# board.net
KiCad netlist of a schematic drawn in EAGLE
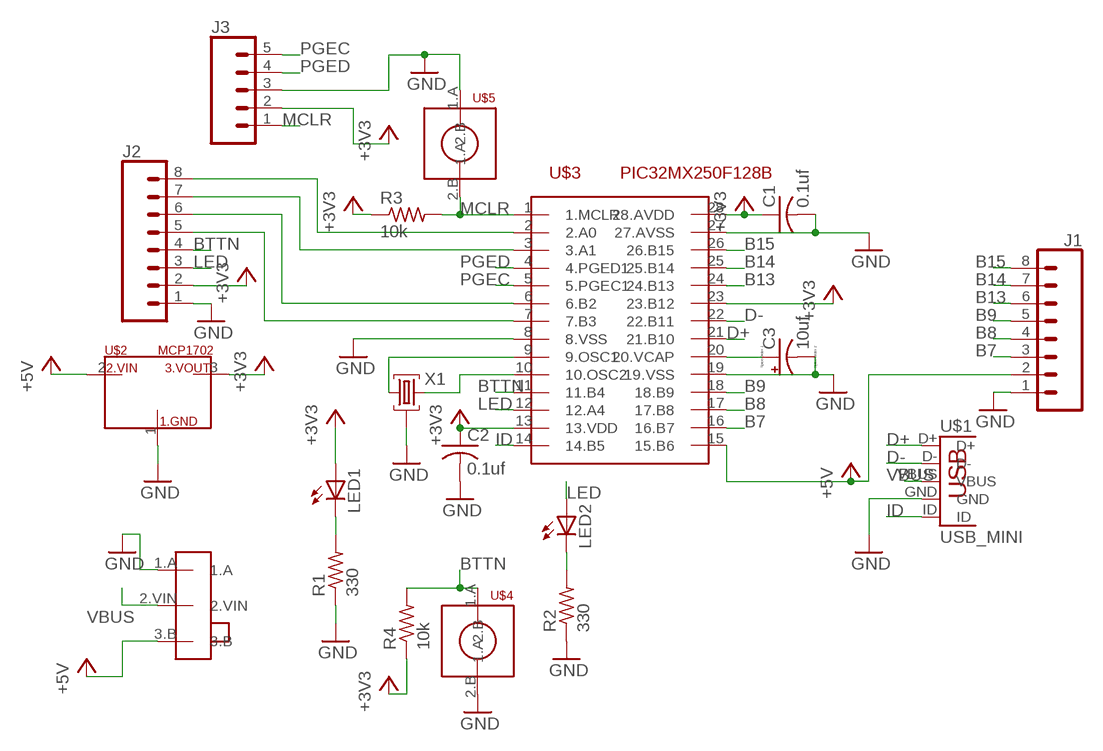
[diagram p0: schematic, sheet 1]

(export (version "E")
  (design (tool "Eeschema 10.0.6"))
  (components
    (comp (ref "C1")
      (value "0.1uf")
      (footprint "eagle-import:C025-025X050")
      (libsource (lib "eagle-import") (part "C-US025-025X050"))
    )
    (comp (ref "C2")
      (value "0.1uf")
      (footprint "eagle-import:C025-025X050")
      (libsource (lib "eagle-import") (part "C-US025-025X050"))
    )
    (comp (ref "C3")
      (value "10uf")
      (footprint "eagle-import:E2,5-6E")
      (libsource (lib "eagle-import") (part "CPOL-USE2,5-6E"))
    )
    (comp (ref "J1")
      (value "CONN_08\"")
      (footprint "eagle-import:1X08")
      (libsource (lib "eagle-import") (part "CONN_08{dblquote}"))
    )
    (comp (ref "J2")
      (value "CONN_08\"")
      (footprint "eagle-import:1X08")
      (libsource (lib "eagle-import") (part "CONN_08{dblquote}"))
    )
    (comp (ref "J3")
      (value "CONN_05")
      (footprint "eagle-import:1X05")
      (libsource (lib "eagle-import") (part "CONN_05"))
    )
    (comp (ref "LED1")
      (value "LED5MM")
      (footprint "eagle-import:LED5MM")
      (libsource (lib "eagle-import") (part "LED5MM"))
    )
    (comp (ref "LED2")
      (value "LED5MM")
      (footprint "eagle-import:LED5MM")
      (libsource (lib "eagle-import") (part "LED5MM"))
    )
    (comp (ref "R1")
      (value "330")
      (footprint "eagle-import:0204_5")
      (libsource (lib "eagle-import") (part "R-US_0204/5"))
    )
    (comp (ref "R2")
      (value "330")
      (footprint "eagle-import:0204_5")
      (libsource (lib "eagle-import") (part "R-US_0204/5"))
    )
    (comp (ref "R3")
      (value "10k")
      (footprint "eagle-import:0204_5")
      (libsource (lib "eagle-import") (part "R-US_0204/5"))
    )
    (comp (ref "R4")
      (value "10k")
      (footprint "eagle-import:0204_5")
      (libsource (lib "eagle-import") (part "R-US_0204/5"))
    )
    (comp (ref "U$1")
      (value "USB_MINI")
      (footprint "eagle-import:USB-MB-H")
      (libsource (lib "eagle-import") (part "USB_MINI"))
    )
    (comp (ref "U$2")
      (value "MCP1702")
      (footprint "eagle-import:TO92")
      (libsource (lib "eagle-import") (part "MCP1702"))
    )
    (comp (ref "U$3")
      (value "PIC32MX250F128B")
      (footprint "eagle-import:DIL28")
      (libsource (lib "eagle-import") (part "PIC32MX250F128B"))
    )
    (comp (ref "U$4")
      (value "PUSH_BUTTON")
      (footprint "eagle-import:PUSH_BUTTON")
      (libsource (lib "eagle-import") (part "PUSH_BUTTON"))
    )
    (comp (ref "U$5")
      (value "PUSH_BUTTON")
      (footprint "eagle-import:PUSH_BUTTON")
      (libsource (lib "eagle-import") (part "PUSH_BUTTON"))
    )
    (comp (ref "U$6")
      (value "SLIDE_SWITCH")
      (footprint "eagle-import:SLIDE_SWITCH")
      (libsource (lib "eagle-import") (part "SLIDE_SWITCH"))
    )
    (comp (ref "X1")
      (value "HC49-HC49-3L")
      (footprint "eagle-import:HC49-3L")
      (libsource (lib "eagle-import") (part "HC49-HC49-3L"))
    )
  )
  (nets
    (net (code "1") (name "+3V3") (class "Default")
      (node (ref "C1") (pin "1") (pinfunction "1_1") (pintype "passive"))
      (node (ref "C2") (pin "1") (pinfunction "1_1") (pintype "passive"))
      (node (ref "J2") (pin "2") (pinfunction "2_2") (pintype "passive"))
      (node (ref "J3") (pin "2") (pinfunction "2_2") (pintype "passive"))
      (node (ref "LED1") (pin "A") (pinfunction "A_A") (pintype "passive"))
      (node (ref "R3") (pin "1") (pinfunction "1_1") (pintype "passive"))
      (node (ref "R4") (pin "1") (pinfunction "1_1") (pintype "passive"))
      (node (ref "U$2") (pin "3") (pinfunction "3.VOUT_3") (pintype "bidirectional"))
      (node (ref "U$3") (pin "13") (pinfunction "13.VDD_13") (pintype "bidirectional"))
      (node (ref "U$3") (pin "23") (pinfunction "23.B12_23") (pintype "bidirectional"))
      (node (ref "U$3") (pin "28") (pinfunction "28.AVDD_28") (pintype "bidirectional"))
    )
    (net (code "2") (name "+5V") (class "Default")
      (node (ref "J1") (pin "2") (pinfunction "2_2") (pintype "passive"))
      (node (ref "U$2") (pin "2") (pinfunction "2.VIN_2") (pintype "bidirectional"))
      (node (ref "U$3") (pin "15") (pinfunction "15.B6_15") (pintype "bidirectional"))
      (node (ref "U$6") (pin "3.B") (pinfunction "3.B_3.B") (pintype "bidirectional"))
    )
    (net (code "3") (name "/B7") (class "Default")
      (node (ref "J1") (pin "3") (pinfunction "3_3") (pintype "passive"))
      (node (ref "U$3") (pin "16") (pinfunction "16.B7_16") (pintype "bidirectional"))
    )
    (net (code "4") (name "/B8") (class "Default")
      (node (ref "J1") (pin "4") (pinfunction "4_4") (pintype "passive"))
      (node (ref "U$3") (pin "17") (pinfunction "17.B8_17") (pintype "bidirectional"))
    )
    (net (code "5") (name "/B9") (class "Default")
      (node (ref "J1") (pin "5") (pinfunction "5_5") (pintype "passive"))
      (node (ref "U$3") (pin "18") (pinfunction "18.B9_18") (pintype "bidirectional"))
    )
    (net (code "6") (name "/B13") (class "Default")
      (node (ref "J1") (pin "6") (pinfunction "6_6") (pintype "passive"))
      (node (ref "U$3") (pin "24") (pinfunction "24.B13_24") (pintype "bidirectional"))
    )
    (net (code "7") (name "/B14") (class "Default")
      (node (ref "J1") (pin "7") (pinfunction "7_7") (pintype "passive"))
      (node (ref "U$3") (pin "25") (pinfunction "25.B14_25") (pintype "bidirectional"))
    )
    (net (code "8") (name "/B15") (class "Default")
      (node (ref "J1") (pin "8") (pinfunction "8_8") (pintype "passive"))
      (node (ref "U$3") (pin "26") (pinfunction "26.B15_26") (pintype "bidirectional"))
    )
    (net (code "9") (name "/BTTN") (class "Default")
      (node (ref "J2") (pin "4") (pinfunction "4_4") (pintype "passive"))
      (node (ref "R4") (pin "2") (pinfunction "2_2") (pintype "passive"))
      (node (ref "U$3") (pin "11") (pinfunction "11.B4_11") (pintype "bidirectional"))
      (node (ref "U$4") (pin "1.A") (pinfunction "1.A_1.A") (pintype "bidirectional"))
    )
    (net (code "10") (name "/D+") (class "Default")
      (node (ref "U$1") (pin "D+") (pinfunction "D+_D+") (pintype "bidirectional"))
      (node (ref "U$3") (pin "21") (pinfunction "21.B10_21") (pintype "bidirectional"))
    )
    (net (code "11") (name "/D-") (class "Default")
      (node (ref "U$1") (pin "D-") (pinfunction "D-_D-") (pintype "bidirectional"))
      (node (ref "U$3") (pin "22") (pinfunction "22.B11_22") (pintype "bidirectional"))
    )
    (net (code "12") (name "/ID") (class "Default")
      (node (ref "U$1") (pin "ID") (pinfunction "ID_ID") (pintype "bidirectional"))
      (node (ref "U$3") (pin "14") (pinfunction "14.B5_14") (pintype "bidirectional"))
    )
    (net (code "13") (name "/LED") (class "Default")
      (node (ref "J2") (pin "3") (pinfunction "3_3") (pintype "passive"))
      (node (ref "LED2") (pin "A") (pinfunction "A_A") (pintype "passive"))
      (node (ref "U$3") (pin "12") (pinfunction "12.A4_12") (pintype "bidirectional"))
    )
    (net (code "14") (name "/MCLR") (class "Default")
      (node (ref "J3") (pin "1") (pinfunction "1_1") (pintype "passive"))
      (node (ref "R3") (pin "2") (pinfunction "2_2") (pintype "passive"))
      (node (ref "U$3") (pin "1") (pinfunction "1.MCLR_1") (pintype "bidirectional"))
      (node (ref "U$5") (pin "2.B") (pinfunction "2.B_2.B") (pintype "bidirectional"))
    )
    (net (code "15") (name "/PGEC") (class "Default")
      (node (ref "J3") (pin "5") (pinfunction "5_5") (pintype "passive"))
      (node (ref "U$3") (pin "5") (pinfunction "5.PGEC1_5") (pintype "bidirectional"))
    )
    (net (code "16") (name "/PGED") (class "Default")
      (node (ref "J3") (pin "4") (pinfunction "4_4") (pintype "passive"))
      (node (ref "U$3") (pin "4") (pinfunction "4.PGED1_4") (pintype "bidirectional"))
    )
    (net (code "17") (name "/VBUS") (class "Default")
      (node (ref "U$1") (pin "VBUS") (pinfunction "VBUS_VBUS") (pintype "bidirectional"))
      (node (ref "U$6") (pin "2.VIN") (pinfunction "2.VIN_2.VIN") (pintype "bidirectional"))
    )
    (net (code "18") (name "GND") (class "Default")
      (node (ref "C1") (pin "2") (pinfunction "2_2") (pintype "passive"))
      (node (ref "C2") (pin "2") (pinfunction "2_2") (pintype "passive"))
      (node (ref "C3") (pin "-") (pinfunction "-_-") (pintype "passive"))
      (node (ref "J1") (pin "1") (pinfunction "1_1") (pintype "passive"))
      (node (ref "J2") (pin "1") (pinfunction "1_1") (pintype "passive"))
      (node (ref "J3") (pin "3") (pinfunction "3_3") (pintype "passive"))
      (node (ref "R1") (pin "1") (pinfunction "1_1") (pintype "passive"))
      (node (ref "R2") (pin "1") (pinfunction "1_1") (pintype "passive"))
      (node (ref "U$1") (pin "GND") (pinfunction "GND_GND") (pintype "bidirectional"))
      (node (ref "U$2") (pin "1") (pinfunction "1.GND_1") (pintype "bidirectional"))
      (node (ref "U$3") (pin "19") (pinfunction "19.VSS_19") (pintype "bidirectional"))
      (node (ref "U$3") (pin "27") (pinfunction "27.AVSS_27") (pintype "bidirectional"))
      (node (ref "U$3") (pin "8") (pinfunction "8.VSS_8") (pintype "bidirectional"))
      (node (ref "U$4") (pin "2.B") (pinfunction "2.B_2.B") (pintype "bidirectional"))
      (node (ref "U$5") (pin "1.A") (pinfunction "1.A_1.A") (pintype "bidirectional"))
      (node (ref "U$6") (pin "1.A") (pinfunction "1.A_1.A") (pintype "bidirectional"))
      (node (ref "X1") (pin "2") (pinfunction "2_2") (pintype "passive"))
    )
    (net (code "19") (name "Net-(LED1-C)") (class "Default")
      (node (ref "LED1") (pin "K") (pinfunction "C_K") (pintype "passive"))
      (node (ref "R1") (pin "2") (pinfunction "2_2") (pintype "passive"))
    )
    (net (code "20") (name "Net-(LED2-C)") (class "Default")
      (node (ref "LED2") (pin "K") (pinfunction "C_K") (pintype "passive"))
      (node (ref "R2") (pin "2") (pinfunction "2_2") (pintype "passive"))
    )
    (net (code "21") (name "Net-(U$3-2.A0)") (class "Default")
      (node (ref "J2") (pin "8") (pinfunction "8_8") (pintype "passive"))
      (node (ref "U$3") (pin "2") (pinfunction "2.A0_2") (pintype "bidirectional"))
    )
    (net (code "22") (name "Net-(U$3-3.A1)") (class "Default")
      (node (ref "J2") (pin "7") (pinfunction "7_7") (pintype "passive"))
      (node (ref "U$3") (pin "3") (pinfunction "3.A1_3") (pintype "bidirectional"))
    )
    (net (code "23") (name "Net-(U$3-6.B2)") (class "Default")
      (node (ref "J2") (pin "6") (pinfunction "6_6") (pintype "passive"))
      (node (ref "U$3") (pin "6") (pinfunction "6.B2_6") (pintype "bidirectional"))
    )
    (net (code "24") (name "Net-(U$3-7.B3)") (class "Default")
      (node (ref "J2") (pin "5") (pinfunction "5_5") (pintype "passive"))
      (node (ref "U$3") (pin "7") (pinfunction "7.B3_7") (pintype "bidirectional"))
    )
    (net (code "25") (name "Net-(U$3-9.OSC1)") (class "Default")
      (node (ref "U$3") (pin "9") (pinfunction "9.OSC1_9") (pintype "bidirectional"))
      (node (ref "X1") (pin "1") (pinfunction "1_1") (pintype "passive"))
    )
    (net (code "26") (name "Net-(U$3-10.OSC2)") (class "Default")
      (node (ref "U$3") (pin "10") (pinfunction "10.OSC2_10") (pintype "bidirectional"))
      (node (ref "X1") (pin "3") (pinfunction "3_3") (pintype "passive"))
    )
    (net (code "27") (name "Net-(U$3-20.VCAP)") (class "Default")
      (node (ref "C3") (pin "+") (pinfunction "+_+") (pintype "passive"))
      (node (ref "U$3") (pin "20") (pinfunction "20.VCAP_20") (pintype "bidirectional"))
    )
  )
)
